# 3v3_Buck.net
KiCad netlist of a schematic drawn in Altium Designer
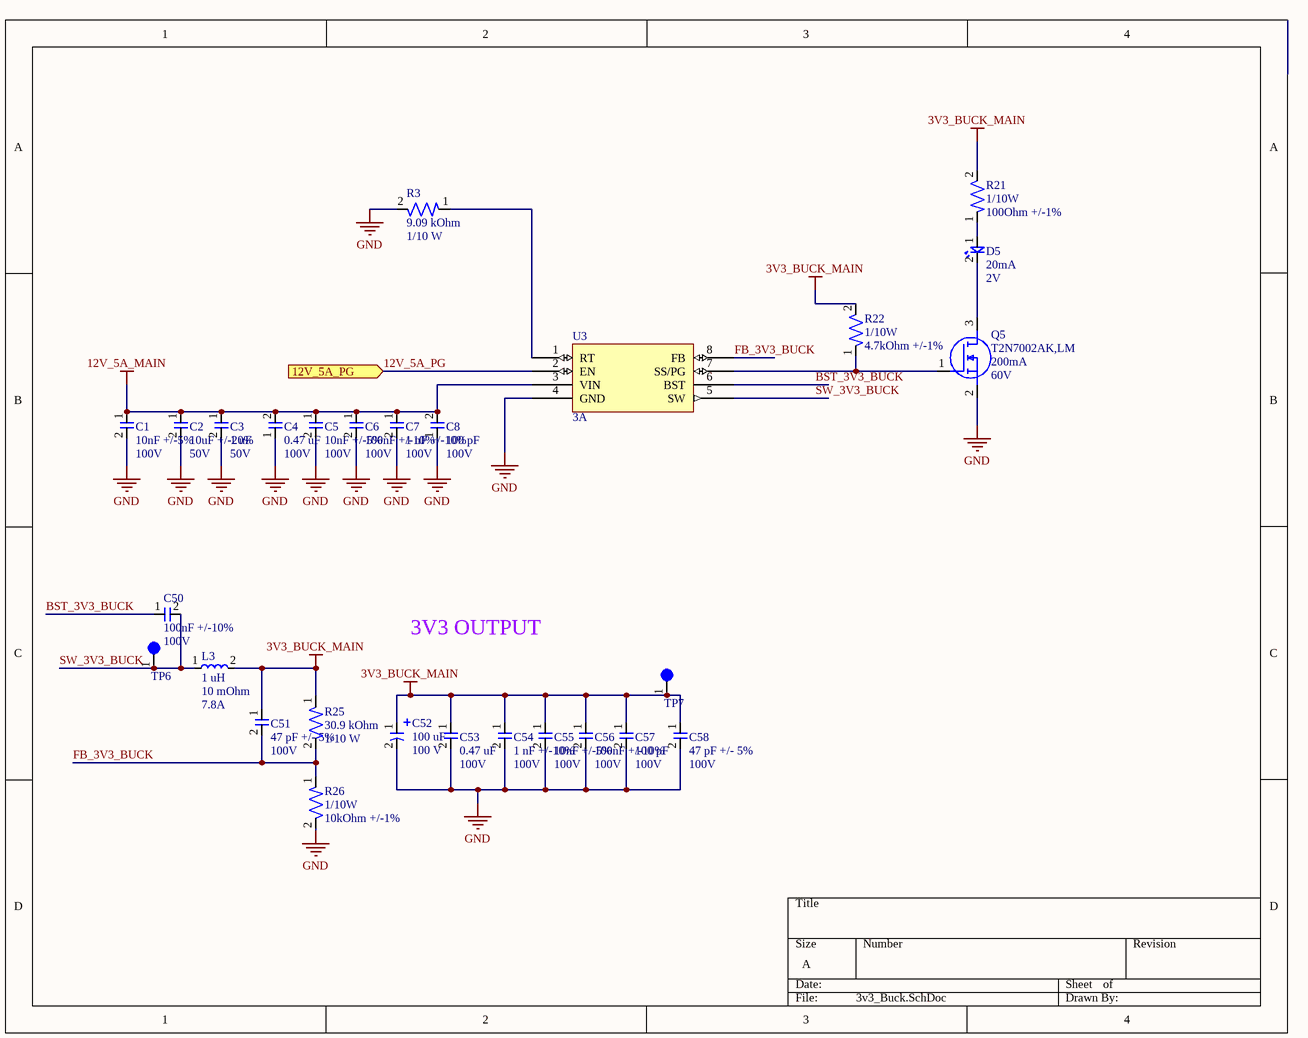
[diagram p0: 3v3_Buck.SchDoc]

(export (version "E")
  (design (tool "Eeschema 10.0.6"))
  (components
    (comp (ref "C1")
      (value "C1608C0G2A103J080AC")
      (footprint "CAP-0603")
      (description "CAP CER 10000PF 100V C0G 0603")
      (fields
        (field (name "MANUFACTURER") "TDK Corporation")
        (field (name "CAPACITANCE") "10nF +/-5%")
        (field (name "VOLTAGE RATING") "100V")
      )
      (libsource (lib "MasterLib") (part "CAP-10N-0002"))
    )
    (comp (ref "C2")
      (value "CL31B106KBHNNNE")
      (footprint "CAP-1206")
      (description "10 µF ±10% 50V Ceramic Capacitor X7R 1206 (3216 Metric)")
      (fields
        (field (name "MANUFACTURER") "Samsung Electro-Mechanics")
        (field (name "CAPACITANCE") "10uF +/-20%")
        (field (name "VOLTAGE RATING") "50V")
      )
      (libsource (lib "MasterLib") (part "CAP-10U-0001"))
    )
    (comp (ref "C3")
      (value "UMK107AB7105KA-T")
      (footprint "CAP-0603")
      (description "1 µF ±10% 50V Ceramic Capacitor X7R 0603 (1608 Metric)")
      (fields (field (name "CAPACITANCE") "1 uF") (field (name "VOLTAGE") "50V"))
      (libsource (lib "MasterLib") (part "CAP-1U-0002"))
    )
    (comp (ref "C4")
      (value "KAM21KR72A474KL")
      (footprint "CAP-0805")
      (description "0.47 µF ±10% 100V Ceramic Capacitor X7R 0805 (2012 Metric)")
      (fields
        (field (name "TOLERANCE") "+/- 10%")
        (field (name "CAPACITANCE") "0.47 uF")
        (field (name "VOLTAGE") "100V")
      )
      (libsource (lib "MasterLib") (part "CAP-0.47U-0001"))
    )
    (comp (ref "C5")
      (value "C1608C0G2A103J080AC")
      (footprint "CAP-0603")
      (description "CAP CER 10000PF 100V C0G 0603")
      (fields
        (field (name "MANUFACTURER") "TDK Corporation")
        (field (name "CAPACITANCE") "10nF +/-5%")
        (field (name "VOLTAGE RATING") "100V")
      )
      (libsource (lib "MasterLib") (part "CAP-10N-0002"))
    )
    (comp (ref "C6")
      (value "CC0603KRX7R0BB104")
      (footprint "CAP-0603")
      (description "CAP CER 0.1UF 100V X7R 0603")
      (fields
        (field (name "MANUFACTURER") "YAGEO")
        (field (name "CAPACITANCE") "100nF +/-10%")
        (field (name "VOLTAGE RATING") "100V")
      )
      (libsource (lib "MasterLib") (part "CAP-100N-0001"))
    )
    (comp (ref "C7")
      (value "C0603Y102K1RAC7867")
      (footprint "CAP-0603")
      (description "1000 pF ±10% 100V Ceramic Capacitor X7R 0603 (1608 Metric)")
      (fields (field (name "CAPACITANCE") "1 nF +/-10%") (field (name "VOLTAGE") "100V"))
      (libsource (lib "MasterLib") (part "CAP-1N-0001"))
    )
    (comp (ref "C8")
      (value "0603N101J101CT")
      (footprint "CAP-0603")
      (description "100 pF ±5% 100V Ceramic Capacitor C0G, NP0 0603 (1608 Metric)")
      (fields
        (field (name "TOLERANCE") "+/-5%")
        (field (name "CAPACITANCE") "100 pF")
        (field (name "VOLTAGE") "100V")
      )
      (libsource (lib "MasterLib") (part "CAP-100P-0002"))
    )
    (comp (ref "C50")
      (value "CC0603KRX7R0BB104")
      (footprint "CAP-0603")
      (description "CAP CER 0.1UF 100V X7R 0603")
      (fields
        (field (name "MANUFACTURER") "YAGEO")
        (field (name "CAPACITANCE") "100nF +/-10%")
        (field (name "VOLTAGE RATING") "100V")
      )
      (libsource (lib "MasterLib") (part "CAP-100N-0001"))
    )
    (comp (ref "C51")
      (value "7447798111")
      (footprint "CAP-0603")
      (description "47 pF ±5% 100V Ceramic Capacitor C0G, NP0 0603 (1608 Metric)")
      (fields (field (name "CAPACITANCE") "47 pF +/- 5%") (field (name "VOLTAGE RATING") "100V"))
      (libsource (lib "MasterLib") (part "CAP-47P-0001"))
    )
    (comp (ref "C52")
      (value "100SEV100M12.5X16")
      (footprint "ELEC-100U-0001")
      (description "100 µF 100 V Aluminum Electrolytic Capacitors Radial, Can - SMD 2000 Hrs @ 85°C")
      (fields
        (field (name "MANUFACTURER") "Rubycon")
        (field (name "TOLERANCE") "+/- 20%")
        (field (name "CAPACITANCE") "100 uF")
        (field (name "VOLTAGE") "100 V")
      )
      (libsource (lib "MasterLib") (part "ELEC-100U-0001"))
    )
    (comp (ref "C53")
      (value "KAM21KR72A474KL")
      (footprint "CAP-0805")
      (description "0.47 µF ±10% 100V Ceramic Capacitor X7R 0805 (2012 Metric)")
      (fields
        (field (name "TOLERANCE") "+/- 10%")
        (field (name "CAPACITANCE") "0.47 uF")
        (field (name "VOLTAGE") "100V")
      )
      (libsource (lib "MasterLib") (part "CAP-0.47U-0001"))
    )
    (comp (ref "C54")
      (value "C0603Y102K1RAC7867")
      (footprint "CAP-0603")
      (description "1000 pF ±10% 100V Ceramic Capacitor X7R 0603 (1608 Metric)")
      (fields (field (name "CAPACITANCE") "1 nF +/-10%") (field (name "VOLTAGE") "100V"))
      (libsource (lib "MasterLib") (part "CAP-1N-0001"))
    )
    (comp (ref "C55")
      (value "C1608C0G2A103J080AC")
      (footprint "CAP-0603")
      (description "CAP CER 10000PF 100V C0G 0603")
      (fields
        (field (name "MANUFACTURER") "TDK Corporation")
        (field (name "CAPACITANCE") "10nF +/-5%")
        (field (name "VOLTAGE RATING") "100V")
      )
      (libsource (lib "MasterLib") (part "CAP-10N-0002"))
    )
    (comp (ref "C56")
      (value "CC0603KRX7R0BB104")
      (footprint "CAP-0603")
      (description "CAP CER 0.1UF 100V X7R 0603")
      (fields
        (field (name "MANUFACTURER") "YAGEO")
        (field (name "CAPACITANCE") "100nF +/-10%")
        (field (name "VOLTAGE RATING") "100V")
      )
      (libsource (lib "MasterLib") (part "CAP-100N-0001"))
    )
    (comp (ref "C57")
      (value "0603N101J101CT")
      (footprint "CAP-0603")
      (description "100 pF ±5% 100V Ceramic Capacitor C0G, NP0 0603 (1608 Metric)")
      (fields
        (field (name "TOLERANCE") "+/-5%")
        (field (name "CAPACITANCE") "100 pF")
        (field (name "VOLTAGE") "100V")
      )
      (libsource (lib "MasterLib") (part "CAP-100P-0002"))
    )
    (comp (ref "C58")
      (value "7447798111")
      (footprint "CAP-0603")
      (description "47 pF ±5% 100V Ceramic Capacitor C0G, NP0 0603 (1608 Metric)")
      (fields (field (name "CAPACITANCE") "47 pF +/- 5%") (field (name "VOLTAGE RATING") "100V"))
      (libsource (lib "MasterLib") (part "CAP-47P-0001"))
    )
    (comp (ref "D5")
      (value "150060AS75000")
      (footprint "LED-0603")
      (description "CAP CER 0.1UF 100V X7R 0603")
      (fields
        (field (name "MANUFACTURER") "Wurth Electronik")
        (field (name "CURRENT RATING") "20mA")
        (field (name "VF") "2V")
      )
      (libsource (lib "MasterLib") (part "LED_Amber_0001"))
    )
    (comp (ref "L3")
      (value "SRN8040-1R0Y")
      (footprint "PWRIND-6.8U-0001")
      (description "1 µH Semi-Shielded Drum Core, Wirewound Inductor 7.8 A 10mOhm Max Nonstandard")
      (fields
        (field (name "TOLERANCE") "30%")
        (field (name "INDUCTANCE") "1 uH")
        (field (name "DCR") "10 mOhm")
        (field (name "DCI") "7.8A")
      )
      (libsource (lib "MasterLib") (part "PWRIND-1U-0001"))
    )
    (comp (ref "Q5")
      (value "T2N7002AK,LM")
      (footprint "NMOS-SOT23-3")
      (description "MOSFET N-CH 60V 200MA SOT23")
      (fields
        (field (name "MANUFACTURER") "Toshiba")
        (field (name "ID-CONTINUOUS") "200mA")
        (field (name "VDS-MAX") "60V")
      )
      (libsource (lib "MasterLib") (part "NMOS-200MA-0001"))
    )
    (comp (ref "R3")
      (value "RC0603FR-079K09L")
      (footprint "RES-0603")
      (description "9.09 kOhms ±1% 0.1W, 1/10W Chip Resistor 0603 (1608 Metric) Moisture Resistant Thick Film")
      (fields
        (field (name "TOLERANCE") "+/-1%")
        (field (name "RESISTANCE") "9.09 kOhm")
        (field (name "POWER") "1/10 W")
      )
      (libsource (lib "MasterLib") (part "RES-9.09K-0001"))
    )
    (comp (ref "R21")
      (value "AC0603FR-10100RL")
      (footprint "RES-0603")
      (description "100 Ohms ±1% 0.1W, 1/10W Chip Resistor 0603 (1608 Metric) Automotive AEC-Q200 Thick Film")
      (fields
        (field (name "MANUFACTURER") "YAGEO")
        (field (name "POWER RATING") "1/10W")
        (field (name "RESISTANCE") "100Ohm +/-1%")
      )
      (libsource (lib "MasterLib") (part "RES-100-0002"))
    )
    (comp (ref "R22")
      (value "AF0603FR-074K7L")
      (footprint "RES-0603")
      (description "RES SMD 4.7K OHM 1% 1/10W 0603")
      (fields
        (field (name "MANUFACTURER") "YAGEO")
        (field (name "POWER RATING") "1/10W")
        (field (name "RESISTANCE") "4.7kOhm +/-1%")
      )
      (libsource (lib "MasterLib") (part "RES-4.7K-0002"))
    )
    (comp (ref "R25")
      (value "RC0603FR-0730K9L")
      (footprint "RES-0603")
      (description "30.9 kOhms ±1% 0.1W, 1/10W Chip Resistor 0603 (1608 Metric) Moisture Resistant Thick Film")
      (fields
        (field (name "TOLERANCE") "1%")
        (field (name "RESISTANCE") "30.9 kOhm")
        (field (name "POWER") "1/10 W")
      )
      (libsource (lib "MasterLib") (part "RES-30.9K-0001"))
    )
    (comp (ref "R26")
      (value "RC0603FR-0710KP")
      (footprint "RES-0603")
      (description "RES SMD 10K OHM 1% 1/10W 0603")
      (fields
        (field (name "MANUFACTURER") "YAGEO")
        (field (name "POWER RATING") "1/10W")
        (field (name "RESISTANCE") "10kOhm +/-1%")
      )
      (libsource (lib "MasterLib") (part "RES-10K-0002"))
    )
    (comp (ref "TP6")
      (value "5003")
      (footprint "TEST-POINT-0001")
      (description "Oranange PC Test Point, Miniature Phoisphor Bronze Silver Plating Through Hole Mounting Type")
      (libsource (lib "MasterLib") (part "TEST-POINT-0001"))
    )
    (comp (ref "TP7")
      (value "5003")
      (footprint "TEST-POINT-0001")
      (description "Oranange PC Test Point, Miniature Phoisphor Bronze Silver Plating Through Hole Mounting Type")
      (libsource (lib "MasterLib") (part "TEST-POINT-0001"))
    )
    (comp (ref "U3")
      (value "TPS62933ODRLR")
      (footprint "IC-SOT583")
      (description "Buck Switching Regulator IC Positive Adjustable 0.8V 1 Output 3A SOT-583")
      (fields (field (name "MANUFACTURER") "Texas Instruments") (field (name "CURRENT") "3A"))
      (libsource (lib "MasterLib") (part "IC-BUCK-0010"))
    )
  )
  (nets
    (net (code "1") (name "/12V_5A_PG") (class "Default")
      (node (ref "U3") (pin "2") (pinfunction "EN_2") (pintype "bidirectional"))
    )
    (net (code "2") (name "/BST_3V3_BUCK") (class "Default")
      (node (ref "C50") (pin "1") (pinfunction "1_1") (pintype "passive"))
      (node (ref "U3") (pin "6") (pinfunction "BST_6") (pintype "power_in"))
    )
    (net (code "3") (name "/FB_3V3_BUCK") (class "Default")
      (node (ref "C51") (pin "2") (pinfunction "2_2") (pintype "passive"))
      (node (ref "R25") (pin "2") (pinfunction "2_2") (pintype "passive"))
      (node (ref "R26") (pin "1") (pinfunction "1_1") (pintype "passive"))
      (node (ref "U3") (pin "8") (pinfunction "FB_8") (pintype "bidirectional"))
    )
    (net (code "4") (name "/SW_3V3_BUCK") (class "Default")
      (node (ref "C50") (pin "2") (pinfunction "2_2") (pintype "passive"))
      (node (ref "L3") (pin "1") (pinfunction "1_1") (pintype "passive"))
      (node (ref "TP6") (pin "1") (pinfunction "0_1") (pintype "passive"))
      (node (ref "U3") (pin "5") (pinfunction "SW_5") (pintype "output"))
    )
    (net (code "5") (name "3V3_BUCK_MAIN") (class "Default")
      (node (ref "C51") (pin "1") (pinfunction "1_1") (pintype "passive"))
      (node (ref "C52") (pin "1") (pinfunction "1_1") (pintype "passive"))
      (node (ref "C53") (pin "1") (pinfunction "1_1") (pintype "passive"))
      (node (ref "C54") (pin "1") (pinfunction "1_1") (pintype "passive"))
      (node (ref "C55") (pin "1") (pinfunction "1_1") (pintype "passive"))
      (node (ref "C56") (pin "1") (pinfunction "1_1") (pintype "passive"))
      (node (ref "C57") (pin "1") (pinfunction "1_1") (pintype "passive"))
      (node (ref "C58") (pin "1") (pinfunction "1_1") (pintype "passive"))
      (node (ref "L3") (pin "2") (pinfunction "2_2") (pintype "passive"))
      (node (ref "R21") (pin "2") (pinfunction "2_2") (pintype "passive"))
      (node (ref "R22") (pin "2") (pinfunction "2_2") (pintype "passive"))
      (node (ref "R25") (pin "1") (pinfunction "1_1") (pintype "passive"))
      (node (ref "TP7") (pin "1") (pinfunction "0_1") (pintype "passive"))
    )
    (net (code "6") (name "12V_5A_MAIN") (class "Default")
      (node (ref "C1") (pin "1") (pinfunction "1_1") (pintype "passive"))
      (node (ref "C2") (pin "1") (pinfunction "1_1") (pintype "passive"))
      (node (ref "C3") (pin "1") (pinfunction "1_1") (pintype "passive"))
      (node (ref "C4") (pin "2") (pinfunction "2_2") (pintype "passive"))
      (node (ref "C5") (pin "1") (pinfunction "1_1") (pintype "passive"))
      (node (ref "C6") (pin "1") (pinfunction "1_1") (pintype "passive"))
      (node (ref "C7") (pin "1") (pinfunction "1_1") (pintype "passive"))
      (node (ref "C8") (pin "2") (pinfunction "2_2") (pintype "passive"))
      (node (ref "U3") (pin "3") (pinfunction "VIN_3") (pintype "power_in"))
    )
    (net (code "7") (name "GND") (class "Default")
      (node (ref "C1") (pin "2") (pinfunction "2_2") (pintype "passive"))
      (node (ref "C2") (pin "2") (pinfunction "2_2") (pintype "passive"))
      (node (ref "C3") (pin "2") (pinfunction "2_2") (pintype "passive"))
      (node (ref "C4") (pin "1") (pinfunction "1_1") (pintype "passive"))
      (node (ref "C5") (pin "2") (pinfunction "2_2") (pintype "passive"))
      (node (ref "C52") (pin "2") (pinfunction "2_2") (pintype "passive"))
      (node (ref "C53") (pin "2") (pinfunction "2_2") (pintype "passive"))
      (node (ref "C54") (pin "2") (pinfunction "2_2") (pintype "passive"))
      (node (ref "C55") (pin "2") (pinfunction "2_2") (pintype "passive"))
      (node (ref "C56") (pin "2") (pinfunction "2_2") (pintype "passive"))
      (node (ref "C57") (pin "2") (pinfunction "2_2") (pintype "passive"))
      (node (ref "C58") (pin "2") (pinfunction "2_2") (pintype "passive"))
      (node (ref "C6") (pin "2") (pinfunction "2_2") (pintype "passive"))
      (node (ref "C7") (pin "2") (pinfunction "2_2") (pintype "passive"))
      (node (ref "C8") (pin "1") (pinfunction "1_1") (pintype "passive"))
      (node (ref "Q5") (pin "2") (pinfunction "S_2") (pintype "passive"))
      (node (ref "R26") (pin "2") (pinfunction "2_2") (pintype "passive"))
      (node (ref "R3") (pin "2") (pinfunction "2_2") (pintype "passive"))
      (node (ref "U3") (pin "4") (pinfunction "GND_4") (pintype "power_in"))
    )
    (net (code "8") (name "Net-(D5-Pad1)") (class "Default")
      (node (ref "D5") (pin "1") (pinfunction "1_1") (pintype "passive"))
      (node (ref "R21") (pin "1") (pinfunction "1_1") (pintype "passive"))
    )
    (net (code "9") (name "Net-(Q5-D)") (class "Default")
      (node (ref "D5") (pin "2") (pinfunction "2_2") (pintype "passive"))
      (node (ref "Q5") (pin "3") (pinfunction "D_3") (pintype "passive"))
    )
    (net (code "10") (name "Net-(Q5-G)") (class "Default")
      (node (ref "Q5") (pin "1") (pinfunction "G_1") (pintype "passive"))
      (node (ref "R22") (pin "1") (pinfunction "1_1") (pintype "passive"))
      (node (ref "U3") (pin "7") (pinfunction "SS/PG_7") (pintype "bidirectional"))
    )
    (net (code "11") (name "Net-(U3-RT)") (class "Default")
      (node (ref "R3") (pin "1") (pinfunction "1_1") (pintype "passive"))
      (node (ref "U3") (pin "1") (pinfunction "RT_1") (pintype "bidirectional"))
    )
  )
)
